# Sensors.net
KiCad netlist of a schematic drawn in Altium Designer
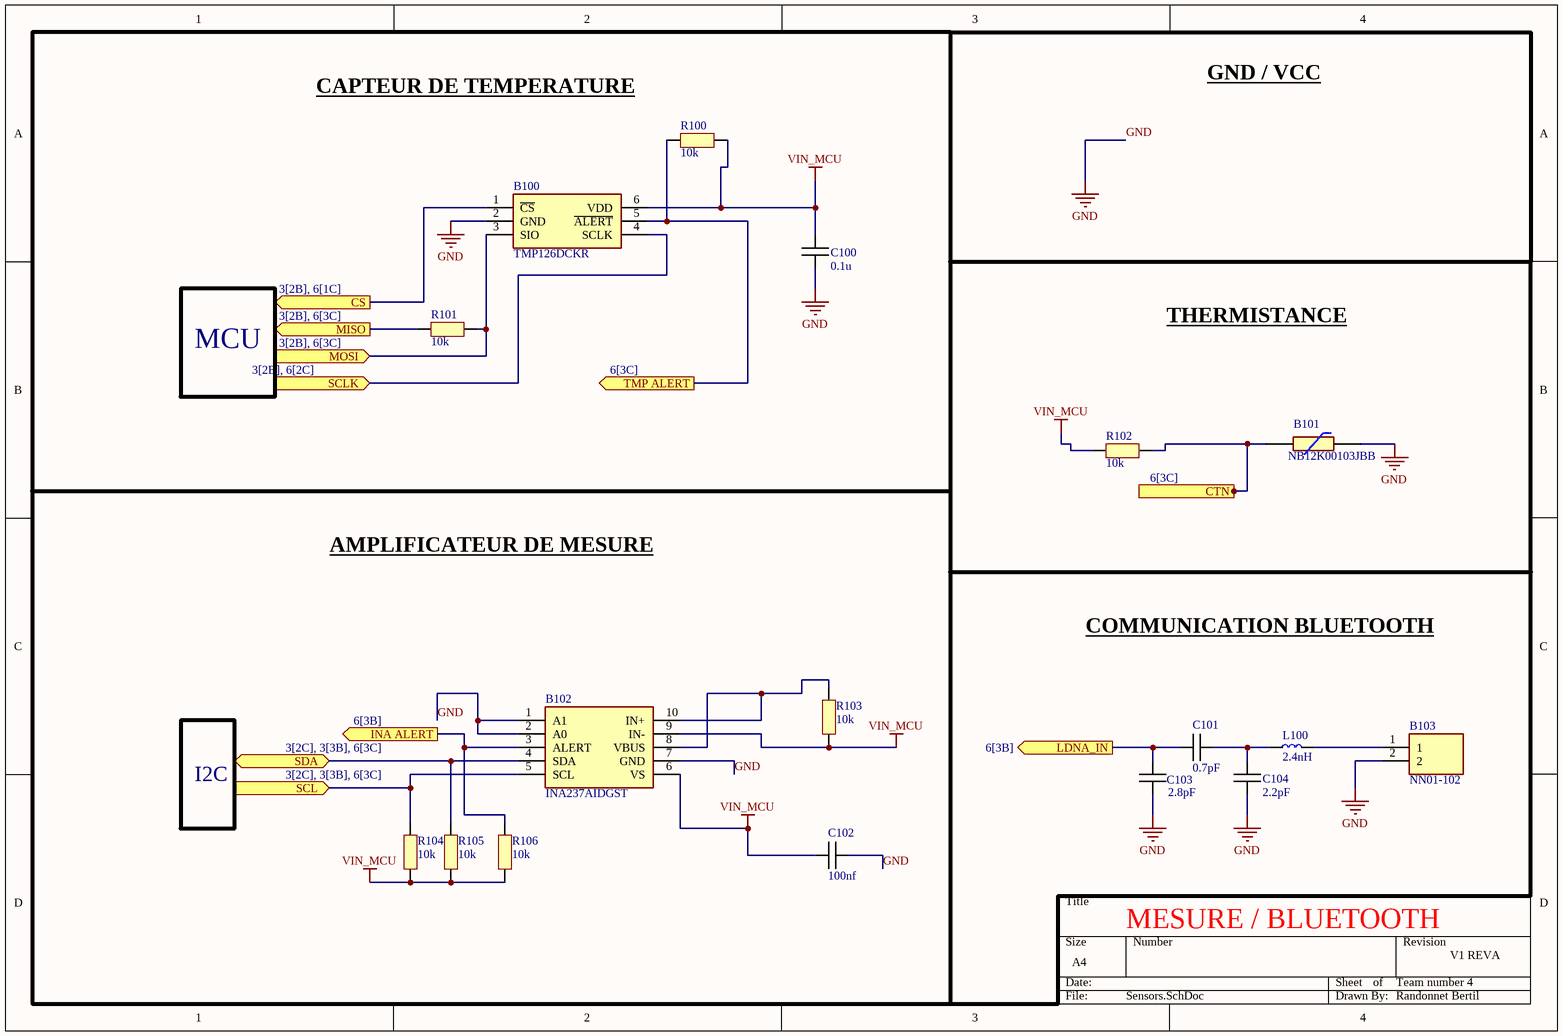
[diagram p0: Sensors.SchDoc]

(export (version "E")
  (design (tool "Eeschema 10.0.6"))
  (components
    (comp (ref "B100")
      (value "TMP126DCKR")
      (footprint "SOT65P210X110-6N")
      (fields (field (name "MOUSER PART NUMBER") "595-TMP126DCKR"))
      (libsource (lib "SCHLibrary") (part "TMP126DCKR"))
    )
    (comp (ref "B101")
      (value "NB12K00103JBB")
      (footprint "RESC2212X50N")
      (description "NTC SMD Thermistor, NB12K, 10K, 5% AVX 10k 0805 Protection NTC Thermistor, 5s, 2 x 1.25 x 1.3mm")
      (fields (field (name "MOUSER PART NUMBER") "581-NB12K00103JBB"))
      (libsource (lib "SCHLibrary") (part "NB12K00103JBB"))
    )
    (comp (ref "B102")
      (value "INA237AIDGST")
      (footprint "SOP50P490X110-10N")
      (fields (field (name "MOUSER PART NUMBER") "595-INA237AIDGST"))
      (libsource (lib "SCHLibrary") (part "INA237AIDGST"))
    )
    (comp (ref "B103")
      (value "NN01-102")
      (footprint "NN01-102")
      (description "Antennes Compact Reach Xtend 2.4 GHz")
      (libsource (lib "SCHLibrary") (part "NN01-102"))
    )
    (comp (ref "C100")
      (value "0.1u")
      (footprint "CAPC1005X06N")
      (libsource (lib "SCHLibrary") (part "Capacitor"))
    )
    (comp (ref "C101")
      (value "0.7pF")
      (footprint "CAPC1005X06N")
      (libsource (lib "SCHLibrary") (part "Capacitor"))
    )
    (comp (ref "C102")
      (value "100nf")
      (footprint "CAPC1005X06N")
      (libsource (lib "SCHLibrary") (part "Capacitor"))
    )
    (comp (ref "C103")
      (value "2.8pF")
      (footprint "CAPC1005X06N")
      (libsource (lib "SCHLibrary") (part "Capacitor"))
    )
    (comp (ref "C104")
      (value "2.2pF")
      (footprint "CAPC1005X06N")
      (libsource (lib "SCHLibrary") (part "Capacitor"))
    )
    (comp (ref "L100")
      (value "2.4nH")
      (footprint "LQPC1005X06N")
      (libsource (lib "SCHLibrary") (part "Bobine"))
    )
    (comp (ref "R100")
      (value "10k")
      (footprint "RESC1005X06N")
      (libsource (lib "SCHLibrary") (part "Resistor"))
    )
    (comp (ref "R101")
      (value "10k")
      (footprint "RESC1005X06N")
      (libsource (lib "SCHLibrary") (part "Resistor"))
    )
    (comp (ref "R102")
      (value "10k")
      (footprint "RESC1005X06N")
      (libsource (lib "SCHLibrary") (part "Resistor"))
    )
    (comp (ref "R103") (value "10k") (footprint "RESC1005X06N") (libsource (lib "") (part "Resistor_1")))
    (comp (ref "R104") (value "10k") (footprint "RESC1005X06N") (libsource (lib "") (part "Resistor_1")))
    (comp (ref "R105") (value "10k") (footprint "RESC1005X06N") (libsource (lib "") (part "Resistor_1")))
    (comp (ref "R106") (value "10k") (footprint "RESC1005X06N") (libsource (lib "") (part "Resistor_1")))
  )
  (nets
    (net (code "1") (name "/CS") (class "Default")
      (node (ref "B100") (pin "1") (pinfunction "~{CS}_1") (pintype "passive"))
    )
    (net (code "2") (name "/CTN") (class "Default")
      (node (ref "B101") (pin "2") (pinfunction "2_2") (pintype "passive"))
      (node (ref "R102") (pin "2") (pinfunction "2_2") (pintype "passive"))
    )
    (net (code "3") (name "/INA ALERT") (class "Default")
      (node (ref "B102") (pin "3") (pinfunction "ALERT_3") (pintype "passive"))
      (node (ref "R106") (pin "2") (pinfunction "2_2") (pintype "passive"))
    )
    (net (code "4") (name "/LDNA_IN") (class "Default")
      (node (ref "C101") (pin "1") (pinfunction "1_1") (pintype "passive"))
      (node (ref "C103") (pin "1") (pinfunction "1_1") (pintype "passive"))
    )
    (net (code "5") (name "/MISO") (class "Default")
      (node (ref "R101") (pin "1") (pinfunction "1_1") (pintype "passive"))
    )
    (net (code "6") (name "/MOSI") (class "Default")
      (node (ref "B100") (pin "3") (pinfunction "SIO_3") (pintype "passive"))
      (node (ref "R101") (pin "2") (pinfunction "2_2") (pintype "passive"))
    )
    (net (code "7") (name "/SCL") (class "Default")
      (node (ref "B102") (pin "5") (pinfunction "SCL_5") (pintype "passive"))
      (node (ref "R104") (pin "2") (pinfunction "2_2") (pintype "passive"))
    )
    (net (code "8") (name "/SCLK") (class "Default")
      (node (ref "B100") (pin "4") (pinfunction "SCLK_4") (pintype "passive"))
    )
    (net (code "9") (name "/SDA") (class "Default")
      (node (ref "B102") (pin "4") (pinfunction "SDA_4") (pintype "passive"))
      (node (ref "R105") (pin "2") (pinfunction "2_2") (pintype "passive"))
    )
    (net (code "10") (name "/TMP ALERT") (class "Default")
      (node (ref "B100") (pin "5") (pinfunction "~{ALERT}_5") (pintype "passive"))
      (node (ref "R100") (pin "1") (pinfunction "1_1") (pintype "passive"))
    )
    (net (code "11") (name "GND") (class "Default")
      (node (ref "B100") (pin "2") (pinfunction "GND_2") (pintype "passive"))
      (node (ref "B101") (pin "1") (pinfunction "1_1") (pintype "passive"))
      (node (ref "B102") (pin "1") (pinfunction "A1_1") (pintype "passive"))
      (node (ref "B102") (pin "2") (pinfunction "A0_2") (pintype "passive"))
      (node (ref "B102") (pin "7") (pinfunction "GND_7") (pintype "passive"))
      (node (ref "B103") (pin "2") (pinfunction "2_2") (pintype "passive"))
      (node (ref "C100") (pin "2") (pinfunction "2_2") (pintype "passive"))
      (node (ref "C102") (pin "1") (pinfunction "1_1") (pintype "passive"))
      (node (ref "C103") (pin "2") (pinfunction "2_2") (pintype "passive"))
      (node (ref "C104") (pin "2") (pinfunction "2_2") (pintype "passive"))
    )
    (net (code "12") (name "Net-(B102-IN+)") (class "Default")
      (node (ref "B102") (pin "10") (pinfunction "IN+_10") (pintype "passive"))
      (node (ref "B102") (pin "8") (pinfunction "VBUS_8") (pintype "passive"))
      (node (ref "R103") (pin "2") (pinfunction "2_2") (pintype "passive"))
    )
    (net (code "13") (name "Net-(B103-Pad1)") (class "Default")
      (node (ref "B103") (pin "1") (pinfunction "1_1") (pintype "passive"))
      (node (ref "L100") (pin "2") (pinfunction "2_2") (pintype "passive"))
    )
    (net (code "14") (name "Net-(C101-Pad2)") (class "Default")
      (node (ref "C101") (pin "2") (pinfunction "2_2") (pintype "passive"))
      (node (ref "C104") (pin "1") (pinfunction "1_1") (pintype "passive"))
      (node (ref "L100") (pin "1") (pinfunction "1_1") (pintype "passive"))
    )
    (net (code "15") (name "VIN_MCU") (class "Default")
      (node (ref "B100") (pin "6") (pinfunction "VDD_6") (pintype "passive"))
      (node (ref "B102") (pin "6") (pinfunction "VS_6") (pintype "passive"))
      (node (ref "B102") (pin "9") (pinfunction "IN-_9") (pintype "passive"))
      (node (ref "C100") (pin "1") (pinfunction "1_1") (pintype "passive"))
      (node (ref "C102") (pin "2") (pinfunction "2_2") (pintype "passive"))
      (node (ref "R100") (pin "2") (pinfunction "2_2") (pintype "passive"))
      (node (ref "R102") (pin "1") (pinfunction "1_1") (pintype "passive"))
      (node (ref "R103") (pin "1") (pinfunction "1_1") (pintype "passive"))
      (node (ref "R104") (pin "1") (pinfunction "1_1") (pintype "passive"))
      (node (ref "R105") (pin "1") (pinfunction "1_1") (pintype "passive"))
      (node (ref "R106") (pin "1") (pinfunction "1_1") (pintype "passive"))
    )
  )
)
